# telemetry_adc.net
KiCad netlist of a schematic drawn in Altium Designer
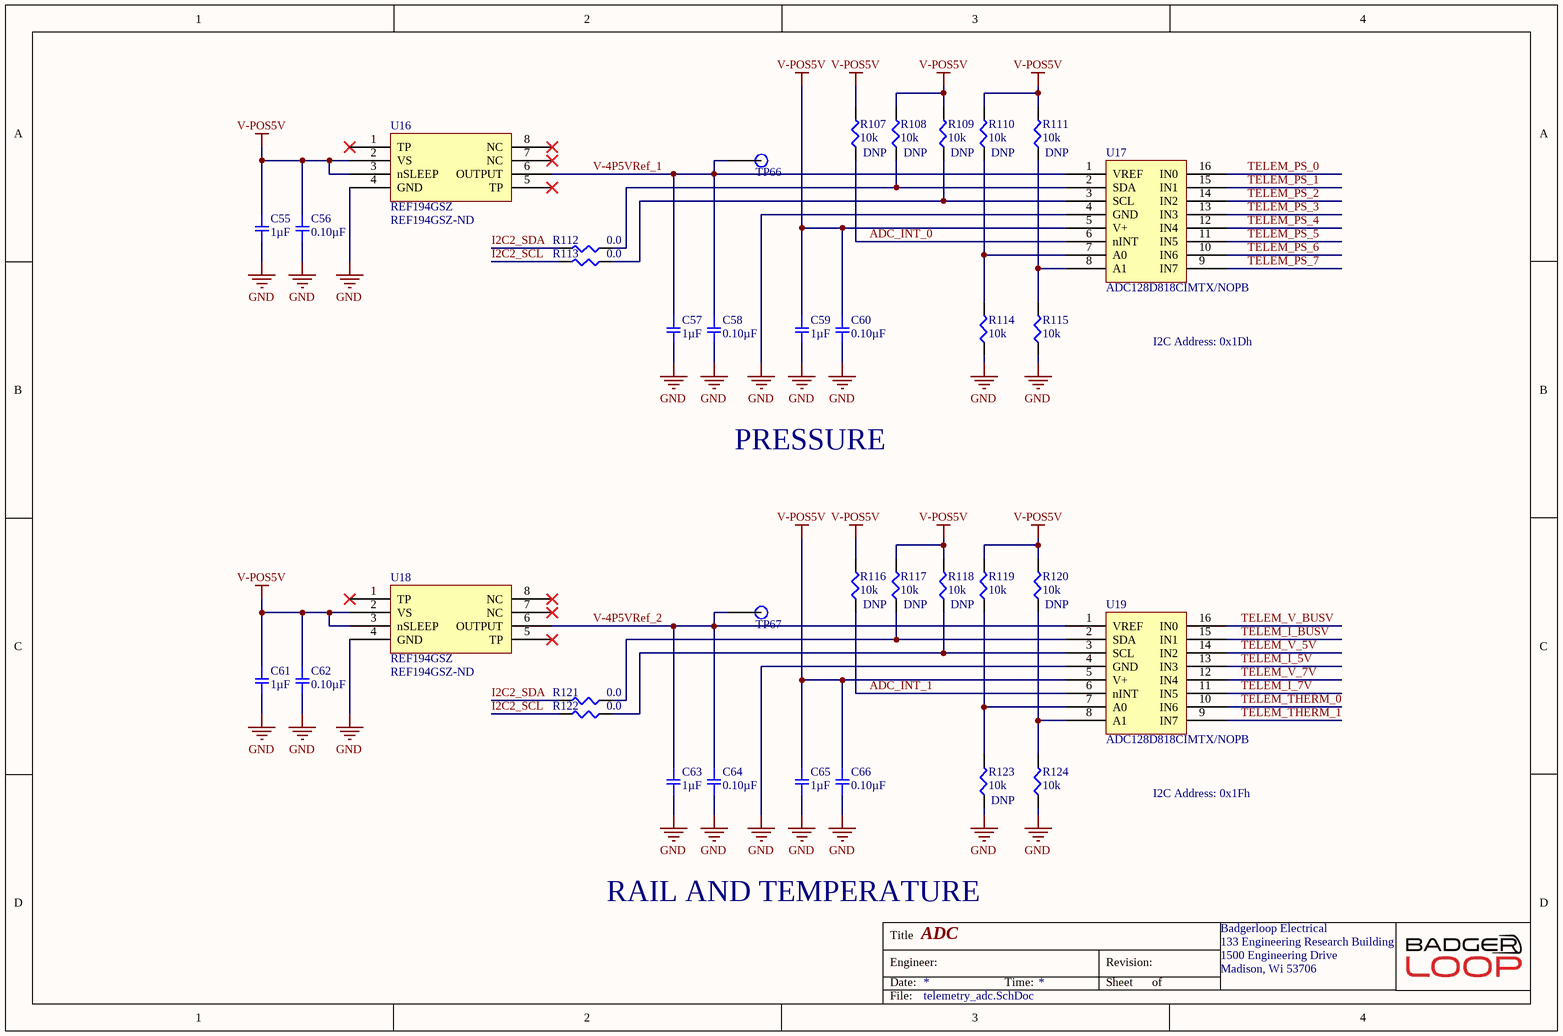
[diagram p0: telemetry_adc.SchDoc]

(export (version "E")
  (design (tool "Eeschema 10.0.6"))
  (components
    (comp (ref "C55")
      (value "1µF")
      (footprint "SMD-0805C")
      (description "CAP CER 1UF 50V X7R 0805")
      (fields
        (field (name "DIGI-KEY PART NUMBER") "490-4736-1-ND")
        (field (name "PART NUMBER") "GRM21BR71H105KA12L")
      )
      (libsource (lib "capacitors") (part "GRM21BR71H105KA12L"))
    )
    (comp (ref "C56")
      (value "0.10µF")
      (footprint "SMD-0805C")
      (description "CAP CER 0.1UF 50V X7R 0805")
      (fields
        (field (name "DIGI-KEY PART NUMBER") "490-11955-1-ND")
        (field (name "PART NUMBER") "GCD21BR71H104KA01L")
      )
      (libsource (lib "capacitors") (part "GCD21BR71H104KA01L"))
    )
    (comp (ref "C57")
      (value "1µF")
      (footprint "SMD-0805C")
      (description "CAP CER 1UF 50V X7R 0805")
      (fields
        (field (name "DIGI-KEY PART NUMBER") "490-4736-1-ND")
        (field (name "PART NUMBER") "GRM21BR71H105KA12L")
      )
      (libsource (lib "capacitors") (part "GRM21BR71H105KA12L"))
    )
    (comp (ref "C58")
      (value "0.10µF")
      (footprint "SMD-0805C")
      (description "CAP CER 0.1UF 50V X7R 0805")
      (fields
        (field (name "DIGI-KEY PART NUMBER") "490-11955-1-ND")
        (field (name "PART NUMBER") "GCD21BR71H104KA01L")
      )
      (libsource (lib "capacitors") (part "GCD21BR71H104KA01L"))
    )
    (comp (ref "C59")
      (value "1µF")
      (footprint "SMD-0805C")
      (description "CAP CER 1UF 50V X7R 0805")
      (fields
        (field (name "DIGI-KEY PART NUMBER") "490-4736-1-ND")
        (field (name "PART NUMBER") "GRM21BR71H105KA12L")
      )
      (libsource (lib "capacitors") (part "GRM21BR71H105KA12L"))
    )
    (comp (ref "C60")
      (value "0.10µF")
      (footprint "SMD-0805C")
      (description "CAP CER 0.1UF 50V X7R 0805")
      (fields
        (field (name "DIGI-KEY PART NUMBER") "490-11955-1-ND")
        (field (name "PART NUMBER") "GCD21BR71H104KA01L")
      )
      (libsource (lib "capacitors") (part "GCD21BR71H104KA01L"))
    )
    (comp (ref "C61")
      (value "1µF")
      (footprint "SMD-0805C")
      (description "CAP CER 1UF 50V X7R 0805")
      (fields
        (field (name "DIGI-KEY PART NUMBER") "490-4736-1-ND")
        (field (name "PART NUMBER") "GRM21BR71H105KA12L")
      )
      (libsource (lib "capacitors") (part "GRM21BR71H105KA12L"))
    )
    (comp (ref "C62")
      (value "0.10µF")
      (footprint "SMD-0805C")
      (description "CAP CER 0.1UF 50V X7R 0805")
      (fields
        (field (name "DIGI-KEY PART NUMBER") "490-11955-1-ND")
        (field (name "PART NUMBER") "GCD21BR71H104KA01L")
      )
      (libsource (lib "capacitors") (part "GCD21BR71H104KA01L"))
    )
    (comp (ref "C63")
      (value "1µF")
      (footprint "SMD-0805C")
      (description "CAP CER 1UF 50V X7R 0805")
      (fields
        (field (name "DIGI-KEY PART NUMBER") "490-4736-1-ND")
        (field (name "PART NUMBER") "GRM21BR71H105KA12L")
      )
      (libsource (lib "capacitors") (part "GRM21BR71H105KA12L"))
    )
    (comp (ref "C64")
      (value "0.10µF")
      (footprint "SMD-0805C")
      (description "CAP CER 0.1UF 50V X7R 0805")
      (fields
        (field (name "DIGI-KEY PART NUMBER") "490-11955-1-ND")
        (field (name "PART NUMBER") "GCD21BR71H104KA01L")
      )
      (libsource (lib "capacitors") (part "GCD21BR71H104KA01L"))
    )
    (comp (ref "C65")
      (value "1µF")
      (footprint "SMD-0805C")
      (description "CAP CER 1UF 50V X7R 0805")
      (fields
        (field (name "DIGI-KEY PART NUMBER") "490-4736-1-ND")
        (field (name "PART NUMBER") "GRM21BR71H105KA12L")
      )
      (libsource (lib "capacitors") (part "GRM21BR71H105KA12L"))
    )
    (comp (ref "C66")
      (value "0.10µF")
      (footprint "SMD-0805C")
      (description "CAP CER 0.1UF 50V X7R 0805")
      (fields
        (field (name "DIGI-KEY PART NUMBER") "490-11955-1-ND")
        (field (name "PART NUMBER") "GCD21BR71H104KA01L")
      )
      (libsource (lib "capacitors") (part "GCD21BR71H104KA01L"))
    )
    (comp (ref "R107")
      (value "10k")
      (footprint "SMD-0805-RES")
      (description "RES SMD 10K OHM 5% 1/2W 0805")
      (fields
        (field (name "PART NUMBER") "ERJ-P06J103V")
        (field (name "DIGI-KEY PART NUMBER") "P10KADCT-ND")
        (field (name "DNP") "DNP")
      )
      (libsource (lib "resistors") (part "ERJ-P06J103V"))
    )
    (comp (ref "R108")
      (value "10k")
      (footprint "SMD-0805-RES")
      (description "RES SMD 10K OHM 5% 1/2W 0805")
      (fields
        (field (name "PART NUMBER") "ERJ-P06J103V")
        (field (name "DIGI-KEY PART NUMBER") "P10KADCT-ND")
        (field (name "DNP") "DNP")
      )
      (libsource (lib "resistors") (part "ERJ-P06J103V"))
    )
    (comp (ref "R109")
      (value "10k")
      (footprint "SMD-0805-RES")
      (description "RES SMD 10K OHM 5% 1/2W 0805")
      (fields
        (field (name "PART NUMBER") "ERJ-P06J103V")
        (field (name "DIGI-KEY PART NUMBER") "P10KADCT-ND")
        (field (name "DNP") "DNP")
      )
      (libsource (lib "resistors") (part "ERJ-P06J103V"))
    )
    (comp (ref "R110")
      (value "10k")
      (footprint "SMD-0805-RES")
      (description "RES SMD 10K OHM 5% 1/2W 0805")
      (fields
        (field (name "PART NUMBER") "ERJ-P06J103V")
        (field (name "DIGI-KEY PART NUMBER") "P10KADCT-ND")
        (field (name "DNP") "DNP")
      )
      (libsource (lib "resistors") (part "ERJ-P06J103V"))
    )
    (comp (ref "R111")
      (value "10k")
      (footprint "SMD-0805-RES")
      (description "RES SMD 10K OHM 5% 1/2W 0805")
      (fields
        (field (name "PART NUMBER") "ERJ-P06J103V")
        (field (name "DIGI-KEY PART NUMBER") "P10KADCT-ND")
        (field (name "DNP") "DNP")
      )
      (libsource (lib "resistors") (part "ERJ-P06J103V"))
    )
    (comp (ref "R112")
      (value "0.0")
      (footprint "SMD-0805-RES")
      (description "RES SMD 0.0 OHM JUMPER 1/8W 0805")
      (fields (field (name "PART NUMBER") "ERJ-6GEY0R00V") (field (name "DIGI-KEY PART NUMBER") "P0.0ACT-ND"))
      (libsource (lib "resistors") (part "ERJ-6GEY0R00V"))
    )
    (comp (ref "R113")
      (value "0.0")
      (footprint "SMD-0805-RES")
      (description "RES SMD 0.0 OHM JUMPER 1/8W 0805")
      (fields (field (name "PART NUMBER") "ERJ-6GEY0R00V") (field (name "DIGI-KEY PART NUMBER") "P0.0ACT-ND"))
      (libsource (lib "resistors") (part "ERJ-6GEY0R00V"))
    )
    (comp (ref "R114")
      (value "10k")
      (footprint "SMD-0805-RES")
      (description "RES SMD 10K OHM 5% 1/2W 0805")
      (fields (field (name "PART NUMBER") "ERJ-P06J103V") (field (name "DIGI-KEY PART NUMBER") "P10KADCT-ND"))
      (libsource (lib "resistors") (part "ERJ-P06J103V"))
    )
    (comp (ref "R115")
      (value "10k")
      (footprint "SMD-0805-RES")
      (description "RES SMD 10K OHM 5% 1/2W 0805")
      (fields (field (name "PART NUMBER") "ERJ-P06J103V") (field (name "DIGI-KEY PART NUMBER") "P10KADCT-ND"))
      (libsource (lib "resistors") (part "ERJ-P06J103V"))
    )
    (comp (ref "R116")
      (value "10k")
      (footprint "SMD-0805-RES")
      (description "RES SMD 10K OHM 5% 1/2W 0805")
      (fields
        (field (name "PART NUMBER") "ERJ-P06J103V")
        (field (name "DIGI-KEY PART NUMBER") "P10KADCT-ND")
        (field (name "DNP") "DNP")
      )
      (libsource (lib "resistors") (part "ERJ-P06J103V"))
    )
    (comp (ref "R117")
      (value "10k")
      (footprint "SMD-0805-RES")
      (description "RES SMD 10K OHM 5% 1/2W 0805")
      (fields
        (field (name "PART NUMBER") "ERJ-P06J103V")
        (field (name "DIGI-KEY PART NUMBER") "P10KADCT-ND")
        (field (name "DNP") "DNP")
      )
      (libsource (lib "resistors") (part "ERJ-P06J103V"))
    )
    (comp (ref "R118")
      (value "10k")
      (footprint "SMD-0805-RES")
      (description "RES SMD 10K OHM 5% 1/2W 0805")
      (fields
        (field (name "PART NUMBER") "ERJ-P06J103V")
        (field (name "DIGI-KEY PART NUMBER") "P10KADCT-ND")
        (field (name "DNP") "DNP")
      )
      (libsource (lib "resistors") (part "ERJ-P06J103V"))
    )
    (comp (ref "R119")
      (value "10k")
      (footprint "SMD-0805-RES")
      (description "RES SMD 10K OHM 5% 1/2W 0805")
      (fields (field (name "PART NUMBER") "ERJ-P06J103V") (field (name "DIGI-KEY PART NUMBER") "P10KADCT-ND"))
      (libsource (lib "resistors") (part "ERJ-P06J103V"))
    )
    (comp (ref "R120")
      (value "10k")
      (footprint "SMD-0805-RES")
      (description "RES SMD 10K OHM 5% 1/2W 0805")
      (fields
        (field (name "PART NUMBER") "ERJ-P06J103V")
        (field (name "DIGI-KEY PART NUMBER") "P10KADCT-ND")
        (field (name "DNP") "DNP")
      )
      (libsource (lib "resistors") (part "ERJ-P06J103V"))
    )
    (comp (ref "R121")
      (value "0.0")
      (footprint "SMD-0805-RES")
      (description "RES SMD 0.0 OHM JUMPER 1/8W 0805")
      (fields (field (name "PART NUMBER") "ERJ-6GEY0R00V") (field (name "DIGI-KEY PART NUMBER") "P0.0ACT-ND"))
      (libsource (lib "resistors") (part "ERJ-6GEY0R00V"))
    )
    (comp (ref "R122")
      (value "0.0")
      (footprint "SMD-0805-RES")
      (description "RES SMD 0.0 OHM JUMPER 1/8W 0805")
      (fields (field (name "PART NUMBER") "ERJ-6GEY0R00V") (field (name "DIGI-KEY PART NUMBER") "P0.0ACT-ND"))
      (libsource (lib "resistors") (part "ERJ-6GEY0R00V"))
    )
    (comp (ref "R123")
      (value "10k")
      (footprint "SMD-0805-RES")
      (description "RES SMD 10K OHM 5% 1/2W 0805")
      (fields
        (field (name "PART NUMBER") "ERJ-P06J103V")
        (field (name "DIGI-KEY PART NUMBER") "P10KADCT-ND")
        (field (name "DNP") "DNP")
      )
      (libsource (lib "resistors") (part "ERJ-P06J103V"))
    )
    (comp (ref "R124")
      (value "10k")
      (footprint "SMD-0805-RES")
      (description "RES SMD 10K OHM 5% 1/2W 0805")
      (fields (field (name "PART NUMBER") "ERJ-P06J103V") (field (name "DIGI-KEY PART NUMBER") "P10KADCT-ND"))
      (libsource (lib "resistors") (part "ERJ-P06J103V"))
    )
    (comp (ref "TP66")
      (value "TP")
      (footprint "Test Point")
      (description "SMD TEST POINT")
      (libsource (lib "misc") (part "TP"))
    )
    (comp (ref "TP67")
      (value "TP")
      (footprint "Test Point")
      (description "SMD TEST POINT")
      (libsource (lib "misc") (part "TP"))
    )
    (comp (ref "U16")
      (value "REF194GSZ")
      (footprint "SOP127P600X175-8N")
      (description "IC VREF SERIES 4.5V 8SOIC")
      (fields
        (field (name "MANUFACTURER") "Analog Devices")
        (field (name "SUPPLIER PART NUMBER 1") "REF194GSZ-ND")
      )
      (libsource (lib "ic") (part "REF194GSZ"))
    )
    (comp (ref "U17")
      (value "ADC128D818CIMTX/NOPB")
      (footprint "TSOP65P660X120-16N")
      (description "Analog to Digital Converters - ADC")
      (fields (field (name "MANUFACTURER") "TI National Semiconductor"))
      (libsource (lib "ic") (part "ADC128D818CIMTX/NOPB"))
    )
    (comp (ref "U18")
      (value "REF194GSZ")
      (footprint "SOP127P600X175-8N")
      (description "IC VREF SERIES 4.5V 8SOIC")
      (fields
        (field (name "MANUFACTURER") "Analog Devices")
        (field (name "SUPPLIER PART NUMBER 1") "REF194GSZ-ND")
      )
      (libsource (lib "ic") (part "REF194GSZ"))
    )
    (comp (ref "U19")
      (value "ADC128D818CIMTX/NOPB")
      (footprint "TSOP65P660X120-16N")
      (description "Analog to Digital Converters - ADC")
      (fields (field (name "MANUFACTURER") "TI National Semiconductor"))
      (libsource (lib "ic") (part "ADC128D818CIMTX/NOPB"))
    )
  )
  (nets
    (net (code "1") (name "/ADC_INT_0") (class "Default")
      (node (ref "R107") (pin "1") (pinfunction "1_1") (pintype "passive"))
      (node (ref "U17") (pin "6") (pinfunction "nINT_6") (pintype "passive"))
    )
    (net (code "2") (name "/ADC_INT_1") (class "Default")
      (node (ref "R116") (pin "1") (pinfunction "1_1") (pintype "passive"))
      (node (ref "U19") (pin "6") (pinfunction "nINT_6") (pintype "passive"))
    )
    (net (code "3") (name "/I2C2_SCL") (class "Default")
      (node (ref "R113") (pin "2") (pinfunction "2_2") (pintype "passive"))
      (node (ref "R122") (pin "2") (pinfunction "2_2") (pintype "passive"))
    )
    (net (code "4") (name "/I2C2_SDA") (class "Default")
      (node (ref "R112") (pin "2") (pinfunction "2_2") (pintype "passive"))
      (node (ref "R121") (pin "2") (pinfunction "2_2") (pintype "passive"))
    )
    (net (code "5") (name "/TELEM_I_5V") (class "Default")
      (node (ref "U19") (pin "13") (pinfunction "IN3_13") (pintype "passive"))
    )
    (net (code "6") (name "/TELEM_I_7V") (class "Default")
      (node (ref "U19") (pin "11") (pinfunction "IN5_11") (pintype "passive"))
    )
    (net (code "7") (name "/TELEM_I_BUSV") (class "Default")
      (node (ref "U19") (pin "15") (pinfunction "IN1_15") (pintype "passive"))
    )
    (net (code "8") (name "/TELEM_PS_0") (class "Default")
      (node (ref "U17") (pin "16") (pinfunction "IN0_16") (pintype "passive"))
    )
    (net (code "9") (name "/TELEM_PS_1") (class "Default")
      (node (ref "U17") (pin "15") (pinfunction "IN1_15") (pintype "passive"))
    )
    (net (code "10") (name "/TELEM_PS_2") (class "Default")
      (node (ref "U17") (pin "14") (pinfunction "IN2_14") (pintype "passive"))
    )
    (net (code "11") (name "/TELEM_PS_3") (class "Default")
      (node (ref "U17") (pin "13") (pinfunction "IN3_13") (pintype "passive"))
    )
    (net (code "12") (name "/TELEM_PS_4") (class "Default")
      (node (ref "U17") (pin "12") (pinfunction "IN4_12") (pintype "passive"))
    )
    (net (code "13") (name "/TELEM_PS_5") (class "Default")
      (node (ref "U17") (pin "11") (pinfunction "IN5_11") (pintype "passive"))
    )
    (net (code "14") (name "/TELEM_PS_6") (class "Default")
      (node (ref "U17") (pin "10") (pinfunction "IN6_10") (pintype "passive"))
    )
    (net (code "15") (name "/TELEM_PS_7") (class "Default")
      (node (ref "U17") (pin "9") (pinfunction "IN7_9") (pintype "passive"))
    )
    (net (code "16") (name "/TELEM_THERM_0") (class "Default")
      (node (ref "U19") (pin "10") (pinfunction "IN6_10") (pintype "passive"))
    )
    (net (code "17") (name "/TELEM_THERM_1") (class "Default")
      (node (ref "U19") (pin "9") (pinfunction "IN7_9") (pintype "passive"))
    )
    (net (code "18") (name "/TELEM_V_5V") (class "Default")
      (node (ref "U19") (pin "14") (pinfunction "IN2_14") (pintype "passive"))
    )
    (net (code "19") (name "/TELEM_V_7V") (class "Default")
      (node (ref "U19") (pin "12") (pinfunction "IN4_12") (pintype "passive"))
    )
    (net (code "20") (name "/TELEM_V_BUSV") (class "Default")
      (node (ref "U19") (pin "16") (pinfunction "IN0_16") (pintype "passive"))
    )
    (net (code "21") (name "/V-4P5VRef_1") (class "Default")
      (node (ref "C57") (pin "1") (pinfunction "1_1") (pintype "passive"))
      (node (ref "C58") (pin "1") (pinfunction "1_1") (pintype "passive"))
      (node (ref "TP66") (pin "1") (pinfunction "1_1") (pintype "passive"))
      (node (ref "U16") (pin "6") (pinfunction "OUTPUT_6") (pintype "passive"))
      (node (ref "U17") (pin "1") (pinfunction "VREF_1") (pintype "passive"))
    )
    (net (code "22") (name "/V-4P5VRef_2") (class "Default")
      (node (ref "C63") (pin "1") (pinfunction "1_1") (pintype "passive"))
      (node (ref "C64") (pin "1") (pinfunction "1_1") (pintype "passive"))
      (node (ref "TP67") (pin "1") (pinfunction "1_1") (pintype "passive"))
      (node (ref "U18") (pin "6") (pinfunction "OUTPUT_6") (pintype "passive"))
      (node (ref "U19") (pin "1") (pinfunction "VREF_1") (pintype "passive"))
    )
    (net (code "23") (name "GND") (class "Default")
      (node (ref "C55") (pin "2") (pinfunction "2_2") (pintype "passive"))
      (node (ref "C56") (pin "2") (pinfunction "2_2") (pintype "passive"))
      (node (ref "C57") (pin "2") (pinfunction "2_2") (pintype "passive"))
      (node (ref "C58") (pin "2") (pinfunction "2_2") (pintype "passive"))
      (node (ref "C59") (pin "2") (pinfunction "2_2") (pintype "passive"))
      (node (ref "C60") (pin "2") (pinfunction "2_2") (pintype "passive"))
      (node (ref "C61") (pin "2") (pinfunction "2_2") (pintype "passive"))
      (node (ref "C62") (pin "2") (pinfunction "2_2") (pintype "passive"))
      (node (ref "C63") (pin "2") (pinfunction "2_2") (pintype "passive"))
      (node (ref "C64") (pin "2") (pinfunction "2_2") (pintype "passive"))
      (node (ref "C65") (pin "2") (pinfunction "2_2") (pintype "passive"))
      (node (ref "C66") (pin "2") (pinfunction "2_2") (pintype "passive"))
      (node (ref "R114") (pin "1") (pinfunction "1_1") (pintype "passive"))
      (node (ref "R115") (pin "1") (pinfunction "1_1") (pintype "passive"))
      (node (ref "R123") (pin "1") (pinfunction "1_1") (pintype "passive"))
      (node (ref "R124") (pin "1") (pinfunction "1_1") (pintype "passive"))
      (node (ref "U16") (pin "4") (pinfunction "GND_4") (pintype "passive"))
      (node (ref "U17") (pin "4") (pinfunction "GND_4") (pintype "passive"))
      (node (ref "U18") (pin "4") (pinfunction "GND_4") (pintype "passive"))
      (node (ref "U19") (pin "4") (pinfunction "GND_4") (pintype "passive"))
    )
    (net (code "24") (name "Net-(U17-A0)") (class "Default")
      (node (ref "R110") (pin "1") (pinfunction "1_1") (pintype "passive"))
      (node (ref "R114") (pin "2") (pinfunction "2_2") (pintype "passive"))
      (node (ref "U17") (pin "7") (pinfunction "A0_7") (pintype "passive"))
    )
    (net (code "25") (name "Net-(U17-A1)") (class "Default")
      (node (ref "R111") (pin "1") (pinfunction "1_1") (pintype "passive"))
      (node (ref "R115") (pin "2") (pinfunction "2_2") (pintype "passive"))
      (node (ref "U17") (pin "8") (pinfunction "A1_8") (pintype "passive"))
    )
    (net (code "26") (name "Net-(U17-SCL)") (class "Default")
      (node (ref "R109") (pin "1") (pinfunction "1_1") (pintype "passive"))
      (node (ref "R113") (pin "1") (pinfunction "1_1") (pintype "passive"))
      (node (ref "U17") (pin "3") (pinfunction "SCL_3") (pintype "passive"))
    )
    (net (code "27") (name "Net-(U17-SDA)") (class "Default")
      (node (ref "R108") (pin "1") (pinfunction "1_1") (pintype "passive"))
      (node (ref "R112") (pin "1") (pinfunction "1_1") (pintype "passive"))
      (node (ref "U17") (pin "2") (pinfunction "SDA_2") (pintype "passive"))
    )
    (net (code "28") (name "Net-(U19-A0)") (class "Default")
      (node (ref "R119") (pin "1") (pinfunction "1_1") (pintype "passive"))
      (node (ref "R123") (pin "2") (pinfunction "2_2") (pintype "passive"))
      (node (ref "U19") (pin "7") (pinfunction "A0_7") (pintype "passive"))
    )
    (net (code "29") (name "Net-(U19-A1)") (class "Default")
      (node (ref "R120") (pin "1") (pinfunction "1_1") (pintype "passive"))
      (node (ref "R124") (pin "2") (pinfunction "2_2") (pintype "passive"))
      (node (ref "U19") (pin "8") (pinfunction "A1_8") (pintype "passive"))
    )
    (net (code "30") (name "Net-(U19-SCL)") (class "Default")
      (node (ref "R118") (pin "1") (pinfunction "1_1") (pintype "passive"))
      (node (ref "R122") (pin "1") (pinfunction "1_1") (pintype "passive"))
      (node (ref "U19") (pin "3") (pinfunction "SCL_3") (pintype "passive"))
    )
    (net (code "31") (name "Net-(U19-SDA)") (class "Default")
      (node (ref "R117") (pin "1") (pinfunction "1_1") (pintype "passive"))
      (node (ref "R121") (pin "1") (pinfunction "1_1") (pintype "passive"))
      (node (ref "U19") (pin "2") (pinfunction "SDA_2") (pintype "passive"))
    )
    (net (code "32") (name "V-POS5V") (class "Default")
      (node (ref "C55") (pin "1") (pinfunction "1_1") (pintype "passive"))
      (node (ref "C56") (pin "1") (pinfunction "1_1") (pintype "passive"))
      (node (ref "C59") (pin "1") (pinfunction "1_1") (pintype "passive"))
      (node (ref "C60") (pin "1") (pinfunction "1_1") (pintype "passive"))
      (node (ref "C61") (pin "1") (pinfunction "1_1") (pintype "passive"))
      (node (ref "C62") (pin "1") (pinfunction "1_1") (pintype "passive"))
      (node (ref "C65") (pin "1") (pinfunction "1_1") (pintype "passive"))
      (node (ref "C66") (pin "1") (pinfunction "1_1") (pintype "passive"))
      (node (ref "R107") (pin "2") (pinfunction "2_2") (pintype "passive"))
      (node (ref "R108") (pin "2") (pinfunction "2_2") (pintype "passive"))
      (node (ref "R109") (pin "2") (pinfunction "2_2") (pintype "passive"))
      (node (ref "R110") (pin "2") (pinfunction "2_2") (pintype "passive"))
      (node (ref "R111") (pin "2") (pinfunction "2_2") (pintype "passive"))
      (node (ref "R116") (pin "2") (pinfunction "2_2") (pintype "passive"))
      (node (ref "R117") (pin "2") (pinfunction "2_2") (pintype "passive"))
      (node (ref "R118") (pin "2") (pinfunction "2_2") (pintype "passive"))
      (node (ref "R119") (pin "2") (pinfunction "2_2") (pintype "passive"))
      (node (ref "R120") (pin "2") (pinfunction "2_2") (pintype "passive"))
      (node (ref "U16") (pin "2") (pinfunction "VS_2") (pintype "passive"))
      (node (ref "U16") (pin "3") (pinfunction "nSLEEP_3") (pintype "passive"))
      (node (ref "U17") (pin "5") (pinfunction "V+_5") (pintype "passive"))
      (node (ref "U18") (pin "2") (pinfunction "VS_2") (pintype "passive"))
      (node (ref "U18") (pin "3") (pinfunction "nSLEEP_3") (pintype "passive"))
      (node (ref "U19") (pin "5") (pinfunction "V+_5") (pintype "passive"))
    )
    (net (code "33") (name "unconnected-(U16-NC-Pad7)") (class "Default")
      (node (ref "U16") (pin "7") (pinfunction "NC_7") (pintype "passive+no_connect"))
    )
    (net (code "34") (name "unconnected-(U16-NC-Pad8)") (class "Default")
      (node (ref "U16") (pin "8") (pinfunction "NC_8") (pintype "passive+no_connect"))
    )
    (net (code "35") (name "unconnected-(U16-TP-Pad1)") (class "Default")
      (node (ref "U16") (pin "1") (pinfunction "TP_1") (pintype "passive+no_connect"))
    )
    (net (code "36") (name "unconnected-(U16-TP-Pad5)") (class "Default")
      (node (ref "U16") (pin "5") (pinfunction "TP_5") (pintype "passive+no_connect"))
    )
    (net (code "37") (name "unconnected-(U18-NC-Pad7)") (class "Default")
      (node (ref "U18") (pin "7") (pinfunction "NC_7") (pintype "passive+no_connect"))
    )
    (net (code "38") (name "unconnected-(U18-NC-Pad8)") (class "Default")
      (node (ref "U18") (pin "8") (pinfunction "NC_8") (pintype "passive+no_connect"))
    )
    (net (code "39") (name "unconnected-(U18-TP-Pad1)") (class "Default")
      (node (ref "U18") (pin "1") (pinfunction "TP_1") (pintype "passive+no_connect"))
    )
    (net (code "40") (name "unconnected-(U18-TP-Pad5)") (class "Default")
      (node (ref "U18") (pin "5") (pinfunction "TP_5") (pintype "passive+no_connect"))
    )
  )
)
